# Sheet3.net
KiCad netlist of a schematic drawn in Altium Designer
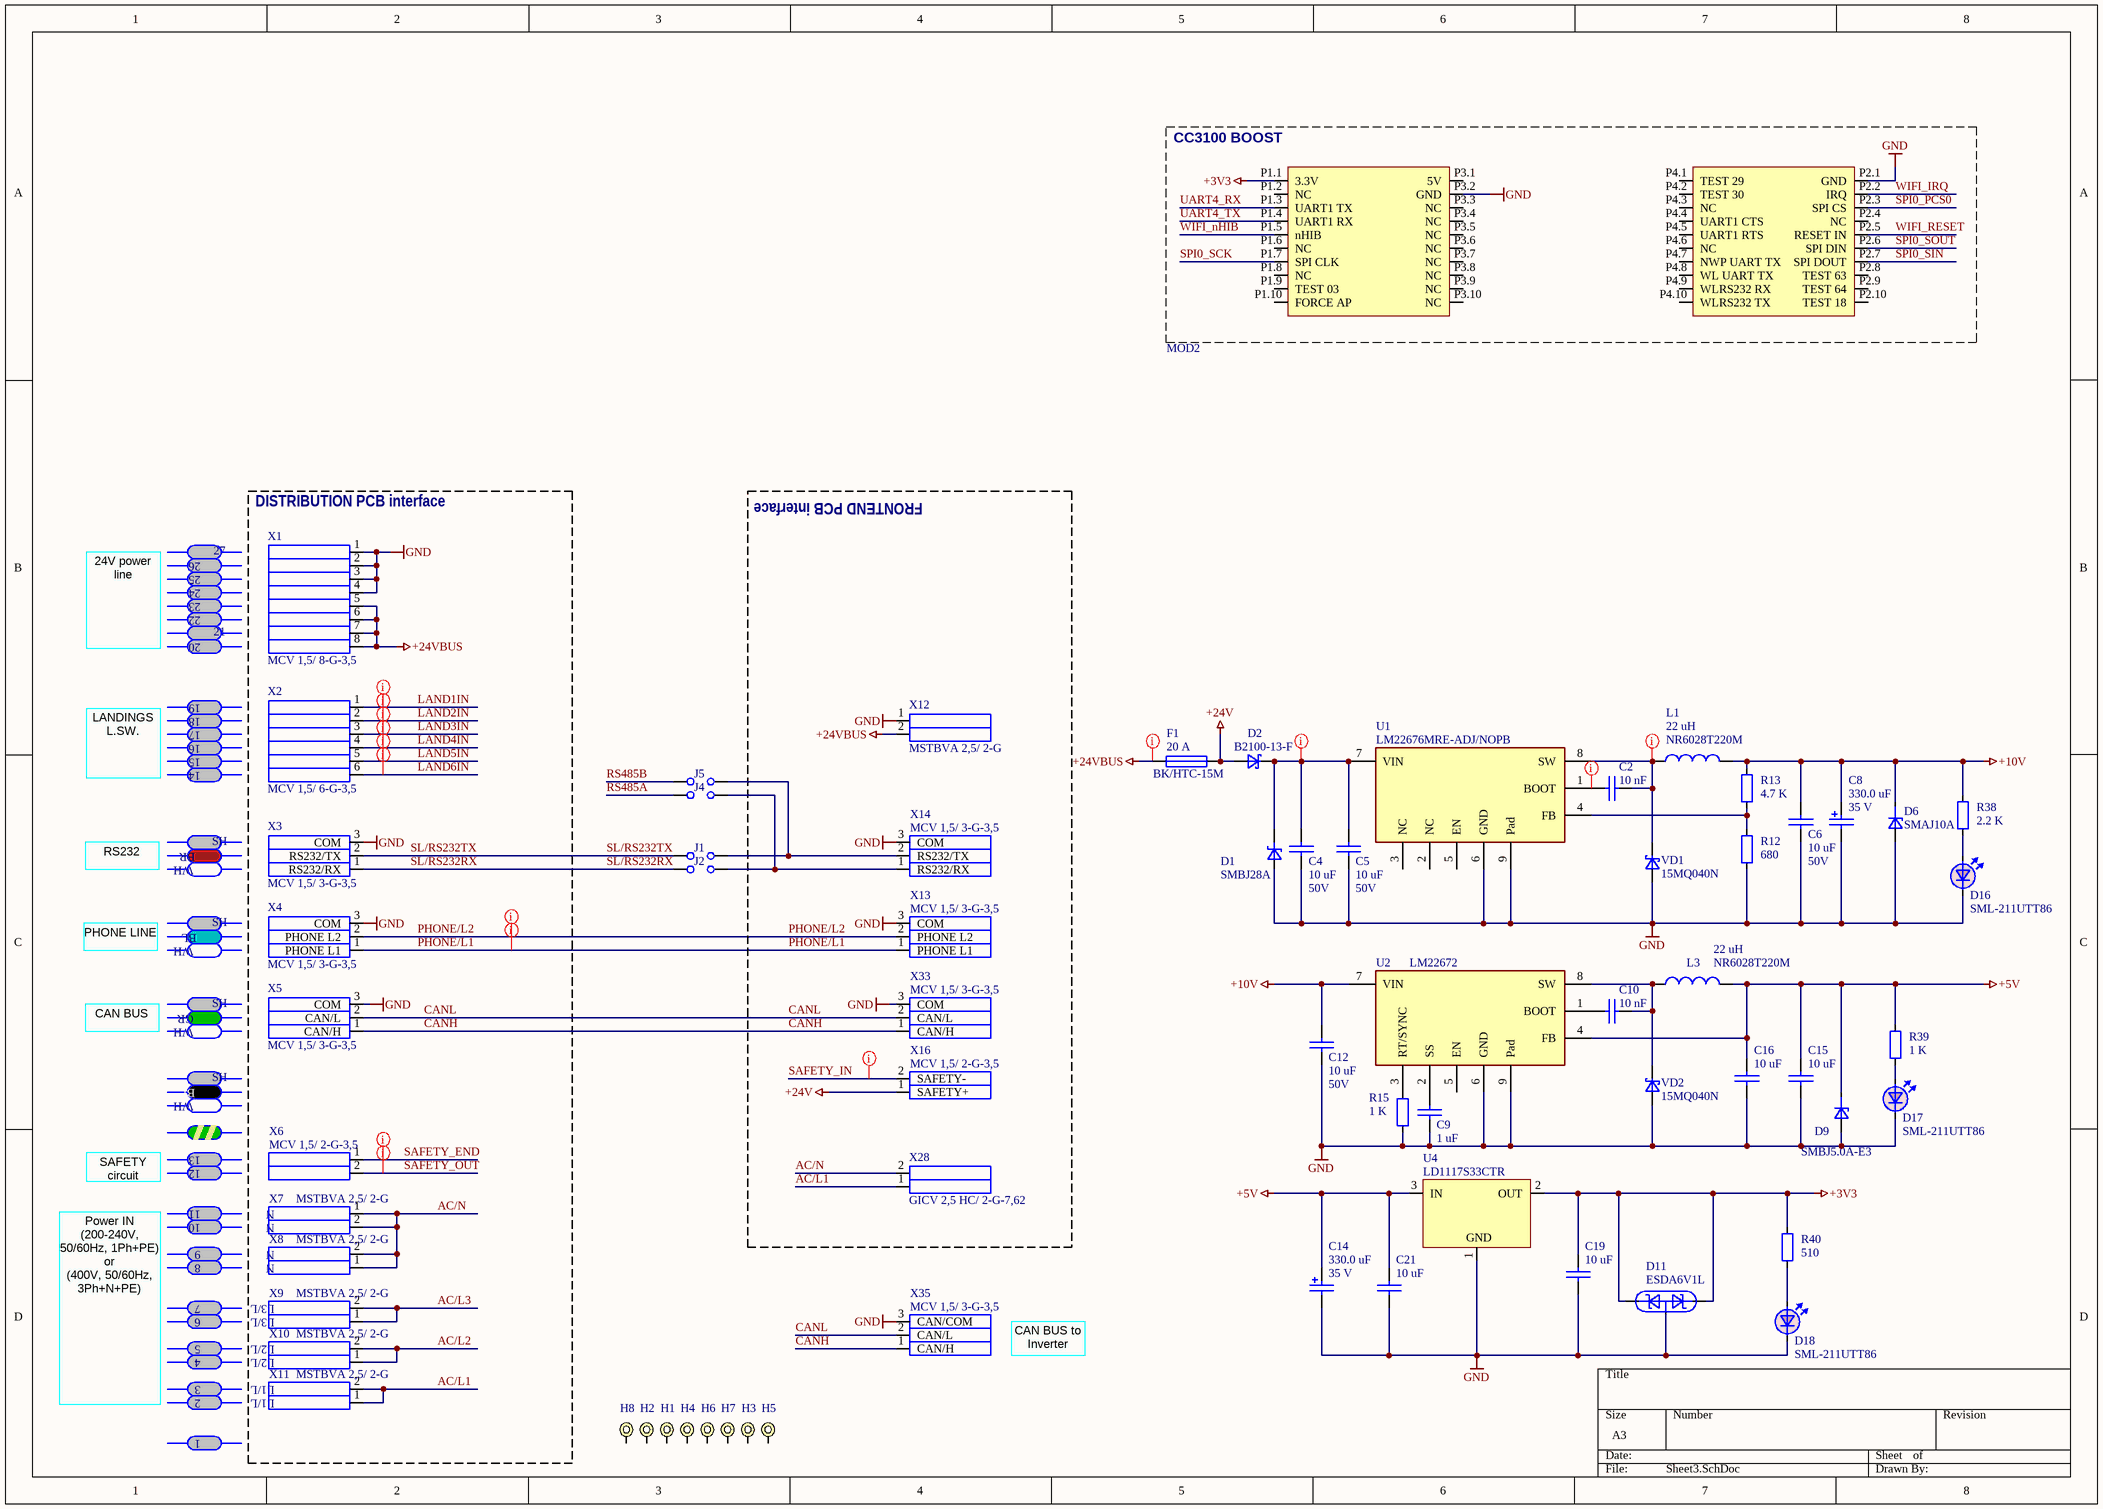
[diagram p0: Sheet3.SchDoc]

(export (version "E")
  (design (tool "Eeschema 10.0.6"))
  (components
    (comp (ref "C2")
      (value "10 nF")
      (footprint "1608[0603]")
      (description "10 nF, 50V, 10%, X7R, 0603 SMD MLC Capacitor")
      (fields (field (name "TOLERANCE") "+-10%") (field (name "MANUFACTURER") "Murata Electronics"))
      (libsource (lib "ea_Capacitors") (part "CVNF010K0603"))
    )
    (comp (ref "C4")
      (value "10 uF")
      (footprint "3225[1210]")
      (description "10uF, 50V, 20%, Y5V (F), 1210")
      (fields
        (field (name "MANUFACTURER") "Taiyo Yuden")
        (field (name "TOLERANCE") "20%")
        (field (name "VOLTAGE") "50V")
      )
      (libsource (lib "ea_Capacitors") (part "GRM32DF51H106ZA01L"))
    )
    (comp (ref "C5")
      (value "10 uF")
      (footprint "3225[1210]")
      (description "10uF, 50V, 20%, Y5V (F), 1210")
      (fields
        (field (name "MANUFACTURER") "Taiyo Yuden")
        (field (name "TOLERANCE") "20%")
        (field (name "VOLTAGE") "50V")
      )
      (libsource (lib "ea_Capacitors") (part "GRM32DF51H106ZA01L"))
    )
    (comp (ref "C6")
      (value "10 uF")
      (footprint "3225[1210]")
      (description "10uF, 50V, 20%, Y5V (F), 1210")
      (fields
        (field (name "MANUFACTURER") "Taiyo Yuden")
        (field (name "TOLERANCE") "20%")
        (field (name "VOLTAGE") "50V")
      )
      (libsource (lib "ea_Capacitors") (part "GRM32DF51H106ZA01L"))
    )
    (comp (ref "C8")
      (value "330.0 uF")
      (footprint "Alum.SMD Cap. 10*10")
      (description "Low ESR SMD alum.el.capacitor 35V, 330uF, 90 mOhm, 670 mA, 10x10, -50...+105 C")
      (fields
        (field (name "MANUFACTURER") "Nichicon")
        (field (name "VOLTAGE") "35 V")
        (field (name "TOLERANCE") "20%")
      )
      (libsource (lib "ea_Capacitors") (part "UUD1V331MNL1GS"))
    )
    (comp (ref "C9")
      (value "1 uF")
      (footprint "2012[0805]")
      (description "1 uF, 10V, 10%, X7R, 0805")
      (fields (field (name "MANUFACTURER") "Murata") (field (name "TOLERANCE") "10%"))
      (libsource (lib "ea_Capacitors") (part "GRM21BR71A105KA01L"))
    )
    (comp (ref "C10")
      (value "10 nF")
      (footprint "1608[0603]")
      (description "10 nF, 50V, 10%, X7R, 0603 SMD MLC Capacitor")
      (fields (field (name "TOLERANCE") "+-10%") (field (name "MANUFACTURER") "Murata Electronics"))
      (libsource (lib "ea_Capacitors") (part "CVNF010K0603"))
    )
    (comp (ref "C12")
      (value "10 uF")
      (footprint "3225[1210]")
      (description "10uF, 50V, 20%, Y5V (F), 1210")
      (fields
        (field (name "MANUFACTURER") "Taiyo Yuden")
        (field (name "TOLERANCE") "20%")
        (field (name "VOLTAGE") "50V")
      )
      (libsource (lib "ea_Capacitors") (part "GRM32DF51H106ZA01L"))
    )
    (comp (ref "C14")
      (value "330.0 uF")
      (footprint "Alum.SMD Cap. 10*10")
      (description "Low ESR SMD alum.el.capacitor 35V, 330uF, 90 mOhm, 670 mA, 10x10, -50...+105 C")
      (fields
        (field (name "MANUFACTURER") "Nichicon")
        (field (name "VOLTAGE") "35 V")
        (field (name "TOLERANCE") "20%")
      )
      (libsource (lib "ea_Capacitors") (part "UUD1V331MNL1GS"))
    )
    (comp (ref "C15")
      (value "10 uF")
      (footprint "0805-1206")
      (description "10 uF, 16V, X5R, ±10%, 0805")
      (fields (field (name "MANUFACTURER") "Taiyo Yuden") (field (name "TOLERANCE") "±10%"))
      (libsource (lib "ea_Capacitors") (part "LMK212F106ZG-T"))
    )
    (comp (ref "C16")
      (value "10 uF")
      (footprint "0805-1206")
      (description "10 uF, 16V, X5R, ±10%, 0805")
      (fields (field (name "MANUFACTURER") "Taiyo Yuden") (field (name "TOLERANCE") "±10%"))
      (libsource (lib "ea_Capacitors") (part "LMK212F106ZG-T"))
    )
    (comp (ref "C19")
      (value "10 uF")
      (footprint "0805-1206")
      (description "10 uF, 16V, X5R, ±10%, 0805")
      (fields (field (name "MANUFACTURER") "Taiyo Yuden") (field (name "TOLERANCE") "±10%"))
      (libsource (lib "ea_Capacitors") (part "LMK212F106ZG-T"))
    )
    (comp (ref "C21")
      (value "10 uF")
      (footprint "0805-1206")
      (description "10 uF, 16V, X5R, ±10%, 0805")
      (fields (field (name "MANUFACTURER") "Taiyo Yuden") (field (name "TOLERANCE") "±10%"))
      (libsource (lib "ea_Capacitors") (part "LMK212F106ZG-T"))
    )
    (comp (ref "D1")
      (value "SMBJ28A")
      (footprint "DO-214AA_SMBJ")
      (description "DIODE TVS 28V 600W UNI 5% SMD")
      (fields (field (name "MANUFACTURER") "Littelfuse") (field (name "PARTNUM") "SMBJ28ABCT-ND"))
      (libsource (lib "ea_TVS_protection") (part "SMBJ28A"))
    )
    (comp (ref "D2")
      (value "B2100-13-F")
      (footprint "SMB ST")
      (description "DIODE SCHOTTKY 100V 2A SMB")
      (fields (field (name "MANUFACTURER") "Diodes Inc") (field (name "PARTNUM") "B2100-FDICT-ND"))
      (libsource (lib "ea_Diodes") (part "B2100-13-F"))
    )
    (comp (ref "D6")
      (value "SMAJ10A")
      (footprint "SMA")
      (description "DIODE TVS 28V 400W UNI 5% SMD")
      (fields (field (name "MANUFACTURER") "Bourns Inc.") (field (name "PARTNUM") "SMAJ10ABCT-ND"))
      (libsource (lib "ea_TVS_protection") (part "SMAJ10A"))
    )
    (comp (ref "D9")
      (value "SMBJ5.0A-E3")
      (footprint "DO-214AA_SMBJ")
      (description "TVS 600W 5.0V Unidirect")
      (fields
        (field (name "MANUFACTURER") "Vishay/General Semiconductor")
        (field (name "PARTNUM") "SMBJ5.0A-E3/52GICT-ND")
      )
      (libsource (lib "ea_TVS_protection") (part "SMBJ5.0A-E3"))
    )
    (comp (ref "D11")
      (value "ESDA6V1L")
      (footprint "SOT23")
      (description "Dual transil array for ESD, 6.1 V, 300 W")
      (fields (field (name "MANUFACTURER") "Micro Commercial Co") (field (name "PARTNUM") "ESDA6V1L-TPCT-ND"))
      (libsource (lib "*") (part "ESDA6V1L"))
    )
    (comp (ref "D16")
      (value "SML-211UTT86")
      (footprint "0805 LED")
      (description "0805 red LED, hibright, 2 mA, 1.8V, 130°")
      (fields (field (name "MANUFACTURER") "Rohm") (field (name "PARTNUM") "511-1292-1-ND"))
      (libsource (lib "ea_Indicators") (part "SML-211UTT86"))
    )
    (comp (ref "D17")
      (value "SML-211UTT86")
      (footprint "0805 LED")
      (description "0805 red LED, hibright, 2 mA, 1.8V, 130°")
      (fields (field (name "MANUFACTURER") "Rohm") (field (name "PARTNUM") "511-1292-1-ND"))
      (libsource (lib "ea_Indicators") (part "SML-211UTT86"))
    )
    (comp (ref "D18")
      (value "SML-211UTT86")
      (footprint "0805 LED")
      (description "0805 red LED, hibright, 2 mA, 1.8V, 130°")
      (fields (field (name "MANUFACTURER") "Rohm") (field (name "PARTNUM") "511-1292-1-ND"))
      (libsource (lib "ea_Indicators") (part "SML-211UTT86"))
    )
    (comp (ref "F1")
      (value "BK/HTC-15M")
      (footprint "FUSE KS21SW")
      (description "FUSE HOLDER KS21SW")
      (fields
        (field (name "MANUFACTURER") "Cooper/Bussmann")
        (field (name "PARTNUM") "283-2923-ND")
        (field (name "ALTIUM_VALUE") "20 A")
      )
      (libsource (lib "ea_Fuses") (part "BK/HTC-15M"))
    )
    (comp (ref "H1")
      (value "Hole 3MM Plated")
      (footprint "HOLE_3MM plated")
      (libsource (lib "ea_Mechanical") (part "Hole 3MM Plated"))
    )
    (comp (ref "H2")
      (value "Hole 3MM Plated")
      (footprint "HOLE_3MM plated")
      (libsource (lib "ea_Mechanical") (part "Hole 3MM Plated"))
    )
    (comp (ref "H3")
      (value "Hole 3MM Plated")
      (footprint "HOLE_3MM plated")
      (libsource (lib "ea_Mechanical") (part "Hole 3MM Plated"))
    )
    (comp (ref "H4")
      (value "Hole 3MM Plated")
      (footprint "HOLE_3MM plated")
      (libsource (lib "ea_Mechanical") (part "Hole 3MM Plated"))
    )
    (comp (ref "H5")
      (value "Hole 3MM Plated")
      (footprint "HOLE_3MM plated")
      (libsource (lib "ea_Mechanical") (part "Hole 3MM Plated"))
    )
    (comp (ref "H6")
      (value "Hole 3MM Plated")
      (footprint "HOLE_3MM plated")
      (libsource (lib "ea_Mechanical") (part "Hole 3MM Plated"))
    )
    (comp (ref "H7")
      (value "Hole 3MM Plated")
      (footprint "HOLE_3MM plated")
      (libsource (lib "ea_Mechanical") (part "Hole 3MM Plated"))
    )
    (comp (ref "H8")
      (value "Hole 3MM Plated")
      (footprint "HOLE_3MM plated")
      (libsource (lib "ea_Mechanical") (part "Hole 3MM Plated"))
    )
    (comp (ref "J1")
      (value "PH1-02-TA-HT")
      (footprint "HDR1X2V")
      (description "2 Pos. 2.54 mm Single Row Through Hole Straight Pin Header")
      (fields (field (name "MANUFACTURER") "ADAM TECH"))
      (libsource (lib "ea_Commutation") (part "Jumper"))
    )
    (comp (ref "J2")
      (value "PH1-02-TA-HT")
      (footprint "HDR1X2V")
      (description "2 Pos. 2.54 mm Single Row Through Hole Straight Pin Header")
      (fields (field (name "MANUFACTURER") "ADAM TECH"))
      (libsource (lib "ea_Commutation") (part "Jumper"))
    )
    (comp (ref "J4")
      (value "PH1-02-TA-HT")
      (footprint "HDR1X2V")
      (description "2 Pos. 2.54 mm Single Row Through Hole Straight Pin Header")
      (fields (field (name "MANUFACTURER") "ADAM TECH"))
      (libsource (lib "ea_Commutation") (part "Jumper"))
    )
    (comp (ref "J5")
      (value "PH1-02-TA-HT")
      (footprint "HDR1X2V")
      (description "2 Pos. 2.54 mm Single Row Through Hole Straight Pin Header")
      (fields (field (name "MANUFACTURER") "ADAM TECH"))
      (libsource (lib "ea_Commutation") (part "Jumper"))
    )
    (comp (ref "L1")
      (value "NR6028T220M")
      (footprint "NR6028 yuden")
      (description "22uH, 1.3 A, 0.175 Ohms, +-20%,- 25 C to + 120 C")
      (fields
        (field (name "MANUFACTURER") "Taiyo Yuden")
        (field (name "PARTNUM") "587-2103-1-ND")
        (field (name "ALTIUM_VALUE") "22 uH")
      )
      (libsource (lib "ea_Inductors") (part "NR6028T220M"))
    )
    (comp (ref "L3")
      (value "NR6028T220M")
      (footprint "NR6028 yuden")
      (description "22uH, 1.3 A, 0.175 Ohms, +-20%,- 25 C to + 120 C")
      (fields
        (field (name "MANUFACTURER") "Taiyo Yuden")
        (field (name "PARTNUM") "587-2103-1-ND")
        (field (name "ALTIUM_VALUE") "22 uH")
      )
      (libsource (lib "ea_Inductors") (part "NR6028T220M"))
    )
    (comp (ref "MOD2")
      (value "CC3100BOOST")
      (footprint "CC3100BOOST")
      (libsource (lib "ea_WiFi_modules") (part "CC3100BOOST"))
    )
    (comp (ref "R12")
      (value "680")
      (footprint "0603")
      (description "680 R, 1%, 0603, SMD Resistor, Taped")
      (fields (field (name "MANUFACTURER") "Vishay") (field (name "TOLERANCE") "1%"))
      (libsource (lib "ea_Resistors") (part "RL0603E680-1"))
    )
    (comp (ref "R13")
      (value "4.7 K")
      (footprint "0603")
      (description "4.7 K, 1%, 0603, SMD Resistor, Taped")
      (fields (field (name "MANUFACTURER") "Vishay") (field (name "TOLERANCE") "1%"))
      (libsource (lib "ea_Resistors") (part "RL0603K004.7-1"))
    )
    (comp (ref "R15")
      (value "1 K")
      (footprint "0603")
      (description "1 K, 1%, 0603, SMD Resistor, Taped")
      (fields (field (name "MANUFACTURER") "YAGEO AMERICA CORPORATION") (field (name "TOLERANCE") "1%"))
      (libsource (lib "ea_Resistors") (part "RL0603K001-1"))
    )
    (comp (ref "R38")
      (value "2.2 K")
      (footprint "0603")
      (description "2.2 K, 1%, 0603, SMD Resistor, Taped")
      (fields (field (name "MANUFACTURER") "YAGEO AMERICA CORPORATION") (field (name "TOLERANCE") "1%"))
      (libsource (lib "ea_Resistors") (part "RL0603K002.2-1"))
    )
    (comp (ref "R39")
      (value "1 K")
      (footprint "0603")
      (description "1 K, 1%, 0603, SMD Resistor, Taped")
      (fields (field (name "MANUFACTURER") "YAGEO AMERICA CORPORATION") (field (name "TOLERANCE") "1%"))
      (libsource (lib "ea_Resistors") (part "RL0603K001-1"))
    )
    (comp (ref "R40")
      (value "510")
      (footprint "0603")
      (description "510 R, 1%, 0603, SMD Resistor, Taped")
      (fields (field (name "MANUFACTURER") "Vishay") (field (name "TOLERANCE") "1%"))
      (libsource (lib "ea_Resistors") (part "RL0603E510-1"))
    )
    (comp (ref "U1")
      (value "LM22676MRE-ADJ/NOPB")
      (footprint "SOIC-8 EDP")
      (description "IC REG SWITCH BUCK 3A ADJ 8PSOP")
      (fields
        (field (name "MANUFACTURER") "National Semiconductor")
        (field (name "PARTNUM") "LM22676MRE-ADJCT-ND")
      )
      (libsource (lib "ea_IC_Power_Reg_Ref_Sw") (part "LM22676MRE-ADJ/NOPB"))
    )
    (comp (ref "U2")
      (value "LM22672")
      (footprint "SOIC-8 EDP")
      (description "SIMPLESWITCH, 1.0A 4.5~42VIN, 8PSOP")
      (fields
        (field (name "MANUFACTURER") "National Semiconductor")
        (field (name "PARTNUM") "LM22672MRE-5.0CT-ND")
      )
      (libsource (lib "ea_IC_Power_Reg_Ref_Sw") (part "LM22672MRE-5.0"))
    )
    (comp (ref "U4")
      (value "LD1117S33CTR")
      (footprint "SOT-223")
      (description "Low drop positive voltage regulator, 3.3 V, 1A, SOT-223")
      (fields (field (name "MANUFACTURER") "STMicroelectronics") (field (name "PARTNUM") "497-1241-1-ND"))
      (libsource (lib "ea_IC_Power_Reg_Ref_Sw") (part "LD1117S33CTR"))
    )
    (comp (ref "VD1")
      (value "15MQ040N")
      (footprint "SMA")
      (description "Schottky Power Rectifier 3A, 40V, SMA")
      (fields (field (name "MANUFACTURER") "VISHAY"))
      (libsource (lib "ea_Diodes") (part "15MQ040N"))
    )
    (comp (ref "VD2")
      (value "15MQ040N")
      (footprint "SMA")
      (description "Schottky Power Rectifier 3A, 40V, SMA")
      (fields (field (name "MANUFACTURER") "VISHAY"))
      (libsource (lib "ea_Diodes") (part "15MQ040N"))
    )
    (comp (ref "X1")
      (value "MCV 1,5/ 8-G-3,5")
      (footprint "mcv1.5-8-g_3.5")
      (description "HEADER, VERTICAL, 3.5MM, 8WAY")
      (fields (field (name "MANUFACTURER") "PHOENIX CONTACT") (field (name "PARTNUM") "1843664"))
      (libsource (lib "ea_Connectors") (part "MCV1.5/8-G-3.5"))
    )
    (comp (ref "X2")
      (value "MCV 1,5/ 6-G-3,5")
      (footprint "mcv1.5-6-g_3.5")
      (description "HEADER, VERTICAL, 3.5MM, 6WAY")
      (fields (field (name "MANUFACTURER") "PHOENIX CONTACT") (field (name "PARTNUM") "1843648"))
      (libsource (lib "ea_Connectors") (part "MCV1.5/6-G-3.5"))
    )
    (comp (ref "X3")
      (value "MCV 1,5/ 3-G-3,5")
      (footprint "mcv1.5-3-g_3.5")
      (description "Header, 8 A, 160 V, 3.5 mm pitch, 3 pos")
      (fields (field (name "MANUFACTURER") "Phoenix Contact") (field (name "PARTNUM") "1843619"))
      (libsource (lib "ea_Connectors") (part "MCV1.5/3-G-3.5"))
    )
    (comp (ref "X4")
      (value "MCV 1,5/ 3-G-3,5")
      (footprint "mcv1.5-3-g_3.5")
      (description "Header, 8 A, 160 V, 3.5 mm pitch, 3 pos")
      (fields (field (name "MANUFACTURER") "Phoenix Contact") (field (name "PARTNUM") "1843619"))
      (libsource (lib "ea_Connectors") (part "MCV1.5/3-G-3.5"))
    )
    (comp (ref "X5")
      (value "MCV 1,5/ 3-G-3,5")
      (footprint "mcv1.5-3-g_3.5")
      (description "Header, 8 A, 160 V, 3.5 mm pitch, 3 pos")
      (fields (field (name "MANUFACTURER") "Phoenix Contact") (field (name "PARTNUM") "1843619"))
      (libsource (lib "ea_Connectors") (part "MCV1.5/3-G-3.5"))
    )
    (comp (ref "X6")
      (value "MCV 1,5/ 2-G-3,5")
      (footprint "mcv1.5-2-g_3.5")
      (description "HEADER, VERTICAL, 3.5MM, 2WAY")
      (fields (field (name "MANUFACTURER") "PHOENIX CONTACT") (field (name "PARTNUM") "1843606"))
      (libsource (lib "") (part "MCV1.5/2-G-3.5_1"))
    )
    (comp (ref "X7")
      (value "MSTBVA 2,5/ 2-G")
      (footprint "CIM020P1")
      (description "TERM BLOCK HEADER 2POS 5.08MM")
      (fields (field (name "MANUFACTURER") "Phoenix Contact") (field (name "PARTNUM") "1755516"))
      (libsource (lib "ea_Connectors") (part "796636-2"))
    )
    (comp (ref "X8")
      (value "MSTBVA 2,5/ 2-G")
      (footprint "CIM020P1")
      (description "TERM BLOCK HEADER 2POS 5.08MM")
      (fields (field (name "MANUFACTURER") "Phoenix Contact") (field (name "PARTNUM") "1755516"))
      (libsource (lib "ea_Connectors") (part "796636-2"))
    )
    (comp (ref "X9")
      (value "MSTBVA 2,5/ 2-G")
      (footprint "CIM020P1")
      (description "TERM BLOCK HEADER 2POS 5.08MM")
      (fields (field (name "MANUFACTURER") "Phoenix Contact") (field (name "PARTNUM") "1755516"))
      (libsource (lib "ea_Connectors") (part "796636-2"))
    )
    (comp (ref "X10")
      (value "MSTBVA 2,5/ 2-G")
      (footprint "CIM020P1")
      (description "TERM BLOCK HEADER 2POS 5.08MM")
      (fields (field (name "MANUFACTURER") "Phoenix Contact") (field (name "PARTNUM") "1755516"))
      (libsource (lib "ea_Connectors") (part "796636-2"))
    )
    (comp (ref "X11")
      (value "MSTBVA 2,5/ 2-G")
      (footprint "CIM020P1")
      (description "TERM BLOCK HEADER 2POS 5.08MM")
      (fields (field (name "MANUFACTURER") "Phoenix Contact") (field (name "PARTNUM") "1755516"))
      (libsource (lib "ea_Connectors") (part "796636-2"))
    )
    (comp (ref "X12")
      (value "MSTBVA 2,5/ 2-G")
      (footprint "CIM020P1")
      (description "TERM BLOCK HEADER 2POS 5.08MM")
      (fields (field (name "MANUFACTURER") "Phoenix Contact") (field (name "PARTNUM") "1755516"))
      (libsource (lib "ea_Connectors") (part "796636-2"))
    )
    (comp (ref "X13")
      (value "MCV 1,5/ 3-G-3,5")
      (footprint "mcv1.5-3-g_3.5")
      (description "Header, 8 A, 160 V, 3.5 mm pitch, 3 pos")
      (fields (field (name "MANUFACTURER") "Phoenix Contact") (field (name "PARTNUM") "1843619"))
      (libsource (lib "ea_Connectors") (part "MCV1.5/3-G-3.5"))
    )
    (comp (ref "X14")
      (value "MCV 1,5/ 3-G-3,5")
      (footprint "mcv1.5-3-g_3.5")
      (description "Header, 8 A, 160 V, 3.5 mm pitch, 3 pos")
      (fields (field (name "MANUFACTURER") "Phoenix Contact") (field (name "PARTNUM") "1843619"))
      (libsource (lib "ea_Connectors") (part "MCV1.5/3-G-3.5"))
    )
    (comp (ref "X16")
      (value "MCV 1,5/ 2-G-3,5")
      (footprint "mcv1.5-2-g_3.5")
      (description "HEADER, VERTICAL, 3.5MM, 2WAY")
      (fields (field (name "MANUFACTURER") "PHOENIX CONTACT") (field (name "PARTNUM") "1843606"))
      (libsource (lib "ea_Connectors") (part "MCV1.5/2-G-3.5"))
    )
    (comp (ref "X28")
      (value "GICV 2,5 HC/ 2-G-7,62")
      (footprint "1756485 GICV 2,5 HC/2 -G-7,62")
      (fields (field (name "MANUFACTURER") "PHOENIX CONTACT") (field (name "PARTNUM") "1756485"))
      (libsource (lib "ea_Connectors_Power") (part "GICV 2,5 HC/ 2-G-7,62"))
    )
    (comp (ref "X33")
      (value "MCV 1,5/ 3-G-3,5")
      (footprint "mcv1.5-3-g_3.5")
      (description "Header, 8 A, 160 V, 3.5 mm pitch, 3 pos")
      (fields (field (name "MANUFACTURER") "Phoenix Contact") (field (name "PARTNUM") "1843619"))
      (libsource (lib "ea_Connectors") (part "MCV1.5/3-G-3.5"))
    )
    (comp (ref "X35")
      (value "MCV 1,5/ 3-G-3,5")
      (footprint "mcv1.5-3-g_3.5")
      (description "Header, 8 A, 160 V, 3.5 mm pitch, 3 pos")
      (fields (field (name "MANUFACTURER") "Phoenix Contact") (field (name "PARTNUM") "1843619"))
      (libsource (lib "ea_Connectors") (part "MCV1.5/3-G-3.5"))
    )
  )
  (nets
    (net (code "1") (name "+3V3") (class "Default")
      (node (ref "C19") (pin "2") (pinfunction "2_2") (pintype "passive"))
      (node (ref "D11") (pin "1") (pintype "passive"))
      (node (ref "D11") (pin "2") (pintype "passive"))
      (node (ref "MOD2") (pin "P1.1") (pinfunction "3.3V_P1.1") (pintype "passive"))
      (node (ref "R40") (pin "2") (pinfunction "2_2") (pintype "passive"))
      (node (ref "U4") (pin "2") (pinfunction "OUT_2") (pintype "power_in"))
    )
    (net (code "2") (name "+5V") (class "Default")
      (node (ref "C14") (pin "1") (pinfunction "1_1") (pintype "passive"))
      (node (ref "C15") (pin "2") (pinfunction "2_2") (pintype "passive"))
      (node (ref "C16") (pin "2") (pinfunction "2_2") (pintype "passive"))
      (node (ref "C21") (pin "2") (pinfunction "2_2") (pintype "passive"))
      (node (ref "D9") (pin "1") (pinfunction "C_1") (pintype "passive"))
      (node (ref "L3") (pin "2") (pinfunction "2_2") (pintype "passive"))
      (node (ref "R39") (pin "2") (pinfunction "2_2") (pintype "passive"))
      (node (ref "U2") (pin "4") (pinfunction "FB_4") (pintype "passive"))
      (node (ref "U4") (pin "3") (pinfunction "IN_3") (pintype "power_in"))
    )
    (net (code "3") (name "+10V") (class "Default")
      (node (ref "C12") (pin "1") (pinfunction "1_1") (pintype "passive"))
      (node (ref "C6") (pin "1") (pinfunction "1_1") (pintype "passive"))
      (node (ref "C8") (pin "1") (pinfunction "1_1") (pintype "passive"))
      (node (ref "D6") (pin "1") (pinfunction "1_1") (pintype "passive"))
      (node (ref "L1") (pin "2") (pinfunction "2_2") (pintype "passive"))
      (node (ref "R13") (pin "2") (pinfunction "2_2") (pintype "passive"))
      (node (ref "R38") (pin "2") (pinfunction "2_2") (pintype "passive"))
      (node (ref "U2") (pin "7") (pinfunction "VIN_7") (pintype "passive"))
    )
    (net (code "4") (name "+24V") (class "Default")
      (node (ref "D2") (pin "1") (pinfunction "A_1") (pintype "passive"))
      (node (ref "F1") (pin "1") (pinfunction "1_1") (pintype "passive"))
      (node (ref "X16") (pin "1") (pinfunction "SAFETY+_1") (pintype "passive"))
    )
    (net (code "5") (name "+24VBUS") (class "Default")
      (node (ref "F1") (pin "2") (pinfunction "2_2") (pintype "passive"))
      (node (ref "X1") (pin "5") (pinfunction "5_5") (pintype "passive"))
      (node (ref "X1") (pin "6") (pinfunction "6_6") (pintype "passive"))
      (node (ref "X1") (pin "7") (pinfunction "7_7") (pintype "passive"))
      (node (ref "X1") (pin "8") (pinfunction "8_8") (pintype "passive"))
      (node (ref "X12") (pin "2") (pinfunction "2_2") (pintype "passive"))
    )
    (net (code "6") (name "/AC{slash}L1") (class "Default")
      (node (ref "X11") (pin "1") (pinfunction "1_1") (pintype "passive"))
      (node (ref "X11") (pin "2") (pinfunction "2_2") (pintype "passive"))
      (node (ref "X28") (pin "1") (pinfunction "1_1") (pintype "passive"))
    )
    (net (code "7") (name "/AC{slash}L2") (class "Default")
      (node (ref "X10") (pin "1") (pinfunction "1_1") (pintype "passive"))
      (node (ref "X10") (pin "2") (pinfunction "2_2") (pintype "passive"))
    )
    (net (code "8") (name "/AC{slash}L3") (class "Default")
      (node (ref "X9") (pin "1") (pinfunction "1_1") (pintype "passive"))
      (node (ref "X9") (pin "2") (pinfunction "2_2") (pintype "passive"))
    )
    (net (code "9") (name "/AC{slash}N") (class "Default")
      (node (ref "X28") (pin "2") (pinfunction "2_2") (pintype "passive"))
      (node (ref "X7") (pin "1") (pinfunction "1_1") (pintype "passive"))
      (node (ref "X7") (pin "2") (pinfunction "2_2") (pintype "passive"))
      (node (ref "X8") (pin "1") (pinfunction "1_1") (pintype "passive"))
      (node (ref "X8") (pin "2") (pinfunction "2_2") (pintype "passive"))
    )
    (net (code "10") (name "/CANH") (class "Default")
      (node (ref "X33") (pin "1") (pinfunction "PHONE_L1_1") (pintype "passive"))
      (node (ref "X35") (pin "1") (pinfunction "PHONE_L1_1") (pintype "passive"))
      (node (ref "X5") (pin "1") (pinfunction "PHONE_L1_1") (pintype "passive"))
    )
    (net (code "11") (name "/CANL") (class "Default")
      (node (ref "X33") (pin "2") (pinfunction "PHONE_L2_2") (pintype "passive"))
      (node (ref "X35") (pin "2") (pinfunction "PHONE_L2_2") (pintype "passive"))
      (node (ref "X5") (pin "2") (pinfunction "PHONE_L2_2") (pintype "passive"))
    )
    (net (code "12") (name "/LAND1IN") (class "Default")
      (node (ref "X2") (pin "1") (pinfunction "1_1") (pintype "passive"))
    )
    (net (code "13") (name "/LAND2IN") (class "Default")
      (node (ref "X2") (pin "2") (pinfunction "2_2") (pintype "passive"))
    )
    (net (code "14") (name "/LAND3IN") (class "Default")
      (node (ref "X2") (pin "3") (pinfunction "3_3") (pintype "passive"))
    )
    (net (code "15") (name "/LAND4IN") (class "Default")
      (node (ref "X2") (pin "4") (pinfunction "4_4") (pintype "passive"))
    )
    (net (code "16") (name "/LAND5IN") (class "Default")
      (node (ref "X2") (pin "5") (pinfunction "5_5") (pintype "passive"))
    )
    (net (code "17") (name "/LAND6IN") (class "Default")
      (node (ref "X2") (pin "6") (pinfunction "6_6") (pintype "passive"))
    )
    (net (code "18") (name "/PHONE{slash}L1") (class "Default")
      (node (ref "X13") (pin "1") (pinfunction "PHONE_L1_1") (pintype "passive"))
      (node (ref "X4") (pin "1") (pinfunction "PHONE_L1_1") (pintype "passive"))
    )
    (net (code "19") (name "/PHONE{slash}L2") (class "Default")
      (node (ref "X13") (pin "2") (pinfunction "PHONE_L2_2") (pintype "passive"))
      (node (ref "X4") (pin "2") (pinfunction "PHONE_L2_2") (pintype "passive"))
    )
    (net (code "20") (name "/RS485A") (class "Default")
      (node (ref "J4") (pin "1") (pinfunction "1_1") (pintype "passive"))
    )
    (net (code "21") (name "/RS485B") (class "Default")
      (node (ref "J5") (pin "1") (pinfunction "1_1") (pintype "passive"))
    )
    (net (code "22") (name "/SAFETY_END") (class "Default") (node (ref "X6") (pin "1") (pintype "passive")))
    (net (code "23") (name "/SAFETY_IN") (class "Default")
      (node (ref "X16") (pin "2") (pinfunction "SAFETY-_2") (pintype "passive"))
    )
    (net (code "24") (name "/SAFETY_OUT") (class "Default") (node (ref "X6") (pin "2") (pintype "passive")))
    (net (code "25") (name "/SL{slash}RS232RX") (class "Default")
      (node (ref "J2") (pin "1") (pinfunction "1_1") (pintype "passive"))
      (node (ref "X3") (pin "1") (pinfunction "PHONE_L1_1") (pintype "passive"))
    )
    (net (code "26") (name "/SL{slash}RS232TX") (class "Default")
      (node (ref "J1") (pin "1") (pinfunction "1_1") (pintype "passive"))
      (node (ref "X3") (pin "2") (pinfunction "PHONE_L2_2") (pintype "passive"))
    )
    (net (code "27") (name "/SPI0_PCS0") (class "Default")
      (node (ref "MOD2") (pin "P2.3") (pinfunction "SPI_CS_P2.3") (pintype "passive"))
    )
    (net (code "28") (name "/SPI0_SCK") (class "Default")
      (node (ref "MOD2") (pin "P1.7") (pinfunction "SPI_CLK_P1.7") (pintype "passive"))
    )
    (net (code "29") (name "/SPI0_SIN") (class "Default")
      (node (ref "MOD2") (pin "P2.7") (pinfunction "SPI_DOUT_P2.7") (pintype "passive"))
    )
    (net (code "30") (name "/SPI0_SOUT") (class "Default")
      (node (ref "MOD2") (pin "P2.6") (pinfunction "SPI_DIN_P2.6") (pintype "passive"))
    )
    (net (code "31") (name "/UART4_RX") (class "Default")
      (node (ref "MOD2") (pin "P1.3") (pinfunction "UART1_TX_P1.3") (pintype "passive"))
    )
    (net (code "32") (name "/UART4_TX") (class "Default")
      (node (ref "MOD2") (pin "P1.4") (pinfunction "UART1_RX_P1.4") (pintype "passive"))
    )
    (net (code "33") (name "/WIFI_IRQ") (class "Default")
      (node (ref "MOD2") (pin "P2.2") (pinfunction "IRQ_P2.2") (pintype "passive"))
    )
    (net (code "34") (name "/WIFI_RESET") (class "Default")
      (node (ref "MOD2") (pin "P2.5") (pinfunction "RESET_IN_P2.5") (pintype "passive"))
    )
    (net (code "35") (name "/WIFI_nHIB") (class "Default")
      (node (ref "MOD2") (pin "P1.5") (pinfunction "nHIB_P1.5") (pintype "passive"))
    )
    (net (code "36") (name "GND") (class "Default")
      (node (ref "C12") (pin "2") (pinfunction "2_2") (pintype "passive"))
      (node (ref "C14") (pin "2") (pinfunction "2_2") (pintype "passive"))
      (node (ref "C15") (pin "1") (pinfunction "1_1") (pintype "passive"))
      (node (ref "C16") (pin "1") (pinfunction "1_1") (pintype "passive"))
      (node (ref "C19") (pin "1") (pinfunction "1_1") (pintype "passive"))
      (node (ref "C21") (pin "1") (pinfunction "1_1") (pintype "passive"))
      (node (ref "C4") (pin "2") (pinfunction "2_2") (pintype "passive"))
      (node (ref "C5") (pin "2") (pinfunction "2_2") (pintype "passive"))
      (node (ref "C6") (pin "2") (pinfunction "2_2") (pintype "passive"))
      (node (ref "C8") (pin "2") (pinfunction "2_2") (pintype "passive"))
      (node (ref "C9") (pin "1") (pinfunction "1_1") (pintype "passive"))
      (node (ref "D1") (pin "2") (pinfunction "A_2") (pintype "passive"))
      (node (ref "D11") (pin "3") (pintype "passive"))
      (node (ref "D16") (pin "2") (pinfunction "2_2") (pintype "passive"))
      (node (ref "D17") (pin "2") (pinfunction "2_2") (pintype "passive"))
      (node (ref "D18") (pin "2") (pinfunction "2_2") (pintype "passive"))
      (node (ref "D6") (pin "2") (pinfunction "2_2") (pintype "passive"))
      (node (ref "D9") (pin "2") (pinfunction "A_2") (pintype "passive"))
      (node (ref "MOD2") (pin "P2.1") (pinfunction "GND_P2.1") (pintype "passive"))
      (node (ref "MOD2") (pin "P3.2") (pinfunction "GND_P3.2") (pintype "passive"))
      (node (ref "R12") (pin "1") (pinfunction "1_1") (pintype "passive"))
      (node (ref "R15") (pin "1") (pinfunction "1_1") (pintype "passive"))
      (node (ref "U1") (pin "6") (pinfunction "GND_6") (pintype "passive"))
      (node (ref "U1") (pin "9") (pinfunction "Pad_9") (pintype "passive"))
      (node (ref "U2") (pin "6") (pinfunction "GND_6") (pintype "passive"))
      (node (ref "U2") (pin "9") (pinfunction "Pad_9") (pintype "passive"))
      (node (ref "U4") (pin "1") (pinfunction "GND_1") (pintype "power_in"))
      (node (ref "VD1") (pin "2") (pinfunction "2_2") (pintype "passive"))
      (node (ref "VD2") (pin "2") (pinfunction "2_2") (pintype "passive"))
      (node (ref "X1") (pin "1") (pinfunction "1_1") (pintype "passive"))
      (node (ref "X1") (pin "2") (pinfunction "2_2") (pintype "passive"))
      (node (ref "X1") (pin "3") (pinfunction "3_3") (pintype "passive"))
      (node (ref "X1") (pin "4") (pinfunction "4_4") (pintype "passive"))
      (node (ref "X12") (pin "1") (pinfunction "1_1") (pintype "passive"))
      (node (ref "X13") (pin "3") (pinfunction "COM_3") (pintype "passive"))
      (node (ref "X14") (pin "3") (pinfunction "COM_3") (pintype "passive"))
      (node (ref "X3") (pin "3") (pinfunction "COM_3") (pintype "passive"))
      (node (ref "X33") (pin "3") (pinfunction "COM_3") (pintype "passive"))
      (node (ref "X35") (pin "3") (pinfunction "COM_3") (pintype "passive"))
      (node (ref "X4") (pin "3") (pinfunction "COM_3") (pintype "passive"))
      (node (ref "X5") (pin "3") (pinfunction "COM_3") (pintype "passive"))
    )
    (net (code "37") (name "Net-(D1-C)") (class "Default")
      (node (ref "C4") (pin "1") (pinfunction "1_1") (pintype "passive"))
      (node (ref "C5") (pin "1") (pinfunction "1_1") (pintype "passive"))
      (node (ref "D1") (pin "1") (pinfunction "C_1") (pintype "passive"))
      (node (ref "D2") (pin "2") (pinfunction "C_2") (pintype "passive"))
      (node (ref "U1") (pin "7") (pinfunction "VIN_7") (pintype "passive"))
    )
    (net (code "38") (name "Net-(D16-Pad1)") (class "Default")
      (node (ref "D16") (pin "1") (pinfunction "1_1") (pintype "passive"))
      (node (ref "R38") (pin "1") (pinfunction "1_1") (pintype "passive"))
    )
    (net (code "39") (name "Net-(D17-Pad1)") (class "Default")
      (node (ref "D17") (pin "1") (pinfunction "1_1") (pintype "passive"))
      (node (ref "R39") (pin "1") (pinfunction "1_1") (pintype "passive"))
    )
    (net (code "40") (name "Net-(D18-Pad1)") (class "Default")
      (node (ref "D18") (pin "1") (pinfunction "1_1") (pintype "passive"))
      (node (ref "R40") (pin "1") (pinfunction "1_1") (pintype "passive"))
    )
    (net (code "41") (name "Net-(U1-BOOT)") (class "Default")
      (node (ref "C2") (pin "2") (pinfunction "2_2") (pintype "passive"))
      (node (ref "U1") (pin "1") (pinfunction "BOOT_1") (pintype "passive"))
    )
    (net (code "42") (name "Net-(U1-FB)") (class "Default")
      (node (ref "R12") (pin "2") (pinfunction "2_2") (pintype "passive"))
      (node (ref "R13") (pin "1") (pinfunction "1_1") (pintype "passive"))
      (node (ref "U1") (pin "4") (pinfunction "FB_4") (pintype "passive"))
    )
    (net (code "43") (name "Net-(U1-SW)") (class "Default")
      (node (ref "C2") (pin "1") (pinfunction "1_1") (pintype "passive"))
      (node (ref "L1") (pin "1") (pinfunction "1_1") (pintype "passive"))
      (node (ref "U1") (pin "8") (pinfunction "SW_8") (pintype "passive"))
      (node (ref "VD1") (pin "1") (pinfunction "1_1") (pintype "passive"))
    )
    (net (code "44") (name "Net-(U2-BOOT)") (class "Default")
      (node (ref "C10") (pin "2") (pinfunction "2_2") (pintype "passive"))
      (node (ref "U2") (pin "1") (pinfunction "BOOT_1") (pintype "passive"))
    )
    (net (code "45") (name "Net-(U2-RT{slash}SYNC)") (class "Default")
      (node (ref "R15") (pin "2") (pinfunction "2_2") (pintype "passive"))
      (node (ref "U2") (pin "3") (pinfunction "RT/SYNC_3") (pintype "passive"))
    )
    (net (code "46") (name "Net-(U2-SS)") (class "Default")
      (node (ref "C9") (pin "2") (pinfunction "2_2") (pintype "passive"))
      (node (ref "U2") (pin "2") (pinfunction "SS_2") (pintype "passive"))
    )
    (net (code "47") (name "Net-(U2-SW)") (class "Default")
      (node (ref "C10") (pin "1") (pinfunction "1_1") (pintype "passive"))
      (node (ref "L3") (pin "1") (pinfunction "1_1") (pintype "passive"))
      (node (ref "U2") (pin "8") (pinfunction "SW_8") (pintype "passive"))
      (node (ref "VD2") (pin "1") (pinfunction "1_1") (pintype "passive"))
    )
    (net (code "48") (name "Net-(X14-PHONE_L1)") (class "Default")
      (node (ref "J2") (pin "2") (pinfunction "2_2") (pintype "passive"))
      (node (ref "J4") (pin "2") (pinfunction "2_2") (pintype "passive"))
      (node (ref "X14") (pin "1") (pinfunction "PHONE_L1_1") (pintype "passive"))
    )
    (net (code "49") (name "Net-(X14-PHONE_L2)") (class "Default")
      (node (ref "J1") (pin "2") (pinfunction "2_2") (pintype "passive"))
      (node (ref "J5") (pin "2") (pinfunction "2_2") (pintype "passive"))
      (node (ref "X14") (pin "2") (pinfunction "PHONE_L2_2") (pintype "passive"))
    )
    (net (code "50") (name "unconnected-(H1-Pad0)") (class "Default")
      (node (ref "H1") (pin "0") (pinfunction "0_0") (pintype "passive"))
    )
    (net (code "51") (name "unconnected-(H2-Pad0)") (class "Default")
      (node (ref "H2") (pin "0") (pinfunction "0_0") (pintype "passive"))
    )
    (net (code "52") (name "unconnected-(H3-Pad0)") (class "Default")
      (node (ref "H3") (pin "0") (pinfunction "0_0") (pintype "passive"))
    )
    (net (code "53") (name "unconnected-(H4-Pad0)") (class "Default")
      (node (ref "H4") (pin "0") (pinfunction "0_0") (pintype "passive"))
    )
    (net (code "54") (name "unconnected-(H5-Pad0)") (class "Default")
      (node (ref "H5") (pin "0") (pinfunction "0_0") (pintype "passive"))
    )
    (net (code "55") (name "unconnected-(H6-Pad0)") (class "Default")
      (node (ref "H6") (pin "0") (pinfunction "0_0") (pintype "passive"))
    )
    (net (code "56") (name "unconnected-(H7-Pad0)") (class "Default")
      (node (ref "H7") (pin "0") (pinfunction "0_0") (pintype "passive"))
    )
    (net (code "57") (name "unconnected-(H8-Pad0)") (class "Default")
      (node (ref "H8") (pin "0") (pinfunction "0_0") (pintype "passive"))
    )
    (net (code "58") (name "unconnected-(MOD2-5V-PadP3.1)") (class "Default")
      (node (ref "MOD2") (pin "P3.1") (pinfunction "5V_P3.1") (pintype "passive"))
    )
    (net (code "59") (name "unconnected-(MOD2-FORCE_AP-PadP1.10)") (class "Default")
      (node (ref "MOD2") (pin "P1.10") (pinfunction "FORCE_AP_P1.10") (pintype "passive"))
    )
    (net (code "60") (name "unconnected-(MOD2-NC-PadP1.2)") (class "Default")
      (node (ref "MOD2") (pin "P1.2") (pinfunction "NC_P1.2") (pintype "passive"))
    )
    (net (code "61") (name "unconnected-(MOD2-NC-PadP1.6)") (class "Default")
      (node (ref "MOD2") (pin "P1.6") (pinfunction "NC_P1.6") (pintype "passive"))
    )
    (net (code "62") (name "unconnected-(MOD2-NC-PadP1.8)") (class "Default")
      (node (ref "MOD2") (pin "P1.8") (pinfunction "NC_P1.8") (pintype "passive"))
    )
    (net (code "63") (name "unconnected-(MOD2-NC-PadP2.4)") (class "Default")
      (node (ref "MOD2") (pin "P2.4") (pinfunction "NC_P2.4") (pintype "passive"))
    )
    (net (code "64") (name "unconnected-(MOD2-NC-PadP3.3)") (class "Default")
      (node (ref "MOD2") (pin "P3.3") (pinfunction "NC_P3.3") (pintype "passive"))
    )
    (net (code "65") (name "unconnected-(MOD2-NC-PadP3.4)") (class "Default")
      (node (ref "MOD2") (pin "P3.4") (pinfunction "NC_P3.4") (pintype "passive"))
    )
    (net (code "66") (name "unconnected-(MOD2-NC-PadP3.5)") (class "Default")
      (node (ref "MOD2") (pin "P3.5") (pinfunction "NC_P3.5") (pintype "passive"))
    )
    (net (code "67") (name "unconnected-(MOD2-NC-PadP3.6)") (class "Default")
      (node (ref "MOD2") (pin "P3.6") (pinfunction "NC_P3.6") (pintype "passive"))
    )
    (net (code "68") (name "unconnected-(MOD2-NC-PadP3.7)") (class "Default")
      (node (ref "MOD2") (pin "P3.7") (pinfunction "NC_P3.7") (pintype "passive"))
    )
    (net (code "69") (name "unconnected-(MOD2-NC-PadP3.8)") (class "Default")
      (node (ref "MOD2") (pin "P3.8") (pinfunction "NC_P3.8") (pintype "passive"))
    )
    (net (code "70") (name "unconnected-(MOD2-NC-PadP3.9)") (class "Default")
      (node (ref "MOD2") (pin "P3.9") (pinfunction "NC_P3.9") (pintype "passive"))
    )
    (net (code "71") (name "unconnected-(MOD2-NC-PadP3.10)") (class "Default")
      (node (ref "MOD2") (pin "P3.10") (pinfunction "NC_P3.10") (pintype "passive"))
    )
    (net (code "72") (name "unconnected-(MOD2-NC-PadP4.3)") (class "Default")
      (node (ref "MOD2") (pin "P4.3") (pinfunction "NC_P4.3") (pintype "passive"))
    )
    (net (code "73") (name "unconnected-(MOD2-NC-PadP4.6)") (class "Default")
      (node (ref "MOD2") (pin "P4.6") (pinfunction "NC_P4.6") (pintype "passive"))
    )
    (net (code "74") (name "unconnected-(MOD2-NWP_UART_TX-PadP4.7)") (class "Default")
      (node (ref "MOD2") (pin "P4.7") (pinfunction "NWP_UART_TX_P4.7") (pintype "passive"))
    )
    (net (code "75") (name "unconnected-(MOD2-TEST_03-PadP1.9)") (class "Default")
      (node (ref "MOD2") (pin "P1.9") (pinfunction "TEST_03_P1.9") (pintype "passive"))
    )
    (net (code "76") (name "unconnected-(MOD2-TEST_18-PadP2.10)") (class "Default")
      (node (ref "MOD2") (pin "P2.10") (pinfunction "TEST_18_P2.10") (pintype "passive"))
    )
    (net (code "77") (name "unconnected-(MOD2-TEST_29-PadP4.1)") (class "Default")
      (node (ref "MOD2") (pin "P4.1") (pinfunction "TEST_29_P4.1") (pintype "passive"))
    )
    (net (code "78") (name "unconnected-(MOD2-TEST_30-PadP4.2)") (class "Default")
      (node (ref "MOD2") (pin "P4.2") (pinfunction "TEST_30_P4.2") (pintype "passive"))
    )
    (net (code "79") (name "unconnected-(MOD2-TEST_63-PadP2.8)") (class "Default")
      (node (ref "MOD2") (pin "P2.8") (pinfunction "TEST_63_P2.8") (pintype "passive"))
    )
    (net (code "80") (name "unconnected-(MOD2-TEST_64-PadP2.9)") (class "Default")
      (node (ref "MOD2") (pin "P2.9") (pinfunction "TEST_64_P2.9") (pintype "passive"))
    )
    (net (code "81") (name "unconnected-(MOD2-UART1_CTS-PadP4.4)") (class "Default")
      (node (ref "MOD2") (pin "P4.4") (pinfunction "UART1_CTS_P4.4") (pintype "passive"))
    )
    (net (code "82") (name "unconnected-(MOD2-UART1_RTS-PadP4.5)") (class "Default")
      (node (ref "MOD2") (pin "P4.5") (pinfunction "UART1_RTS_P4.5") (pintype "passive"))
    )
    (net (code "83") (name "unconnected-(MOD2-WLRS232_RX-PadP4.9)") (class "Default")
      (node (ref "MOD2") (pin "P4.9") (pinfunction "WLRS232_RX_P4.9") (pintype "passive"))
    )
    (net (code "84") (name "unconnected-(MOD2-WLRS232_TX-PadP4.10)") (class "Default")
      (node (ref "MOD2") (pin "P4.10") (pinfunction "WLRS232_TX_P4.10") (pintype "passive"))
    )
    (net (code "85") (name "unconnected-(MOD2-WL_UART_TX-PadP4.8)") (class "Default")
      (node (ref "MOD2") (pin "P4.8") (pinfunction "WL_UART_TX_P4.8") (pintype "passive"))
    )
    (net (code "86") (name "unconnected-(U1-EN-Pad5)") (class "Default")
      (node (ref "U1") (pin "5") (pinfunction "EN_5") (pintype "passive"))
    )
    (net (code "87") (name "unconnected-(U1-NC-Pad2)") (class "Default")
      (node (ref "U1") (pin "2") (pinfunction "NC_2") (pintype "passive"))
    )
    (net (code "88") (name "unconnected-(U1-NC-Pad3)") (class "Default")
      (node (ref "U1") (pin "3") (pinfunction "NC_3") (pintype "passive"))
    )
    (net (code "89") (name "unconnected-(U2-EN-Pad5)") (class "Default")
      (node (ref "U2") (pin "5") (pinfunction "EN_5") (pintype "passive"))
    )
  )
)
